# piezo-preamp-tickler_V2-RevA-01.net
KiCad netlist of a schematic drawn in EAGLE
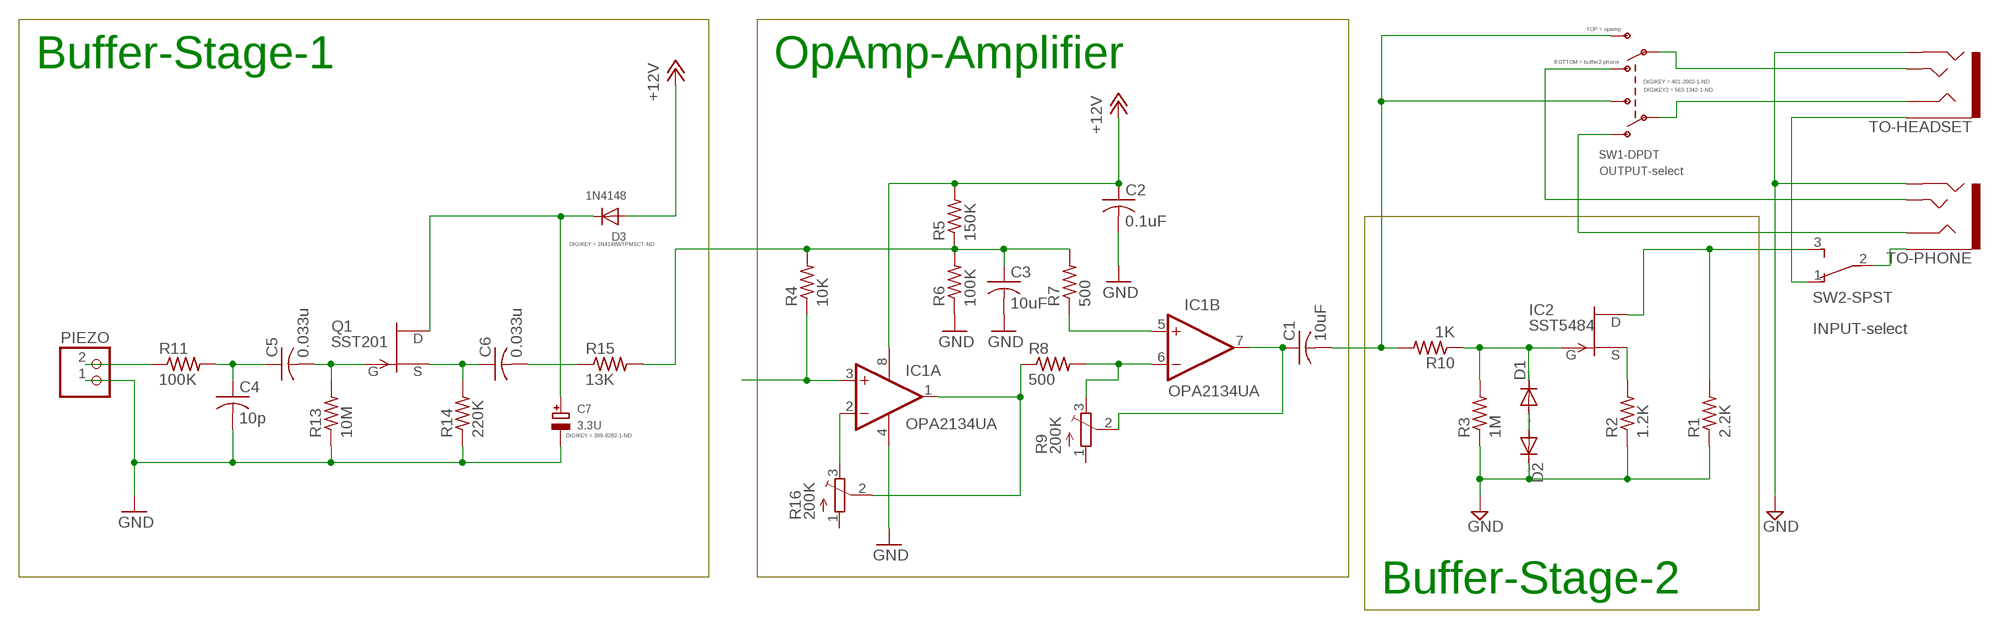
[diagram p0: schematic, sheet 1]
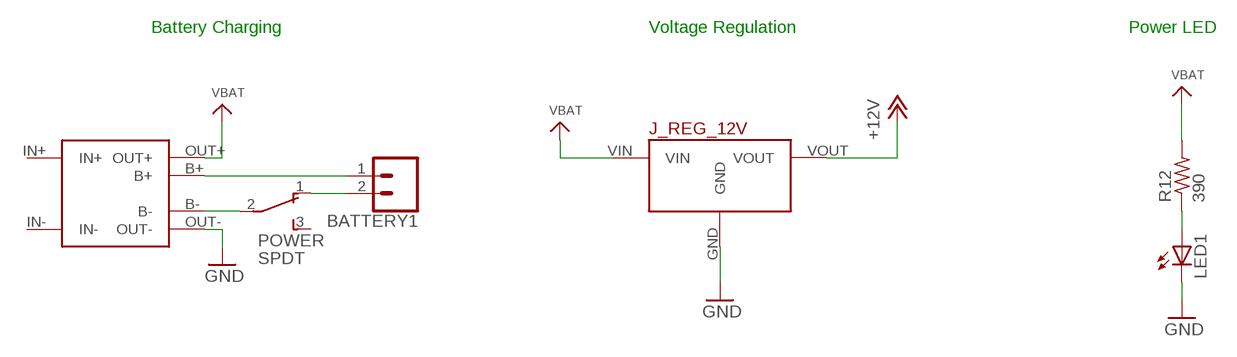
[diagram p1: schematic, sheet 2]

(export (version "E")
  (design (tool "Eeschema 10.0.6"))
  (components
    (comp (ref "C1")
      (value "10uF")
      (footprint "eagle-import:C0805K")
      (libsource (lib "eagle-import") (part "C-USC0805K"))
    )
    (comp (ref "C2")
      (value "0.1uF")
      (footprint "eagle-import:C0805K")
      (libsource (lib "eagle-import") (part "C-USC0805K"))
    )
    (comp (ref "C3")
      (value "10uF")
      (footprint "eagle-import:C0805K")
      (libsource (lib "eagle-import") (part "C-USC0805K"))
    )
    (comp (ref "C4")
      (value "10p")
      (footprint "eagle-import:C0805K")
      (libsource (lib "eagle-import") (part "C-USC0805K"))
    )
    (comp (ref "C5")
      (value "0.033u")
      (footprint "eagle-import:C0805K")
      (libsource (lib "eagle-import") (part "C-USC0805K"))
    )
    (comp (ref "C6")
      (value "0.033u")
      (footprint "eagle-import:C0805K")
      (libsource (lib "eagle-import") (part "C-USC0805K"))
    )
    (comp (ref "C7")
      (value "3.3U")
      (footprint "eagle-import:EIA3216-18_A-R")
      (fields (field (name "DIGIKEY") "399-8282-1-ND"))
      (libsource (lib "eagle-import") (part "CAP_TANTALUMA/3216_REFLOW"))
    )
    (comp (ref "D1")
      (value "DIODE-SOD123")
      (footprint "eagle-import:SOD123")
      (libsource (lib "eagle-import") (part "DIODE-SOD123"))
    )
    (comp (ref "D2")
      (value "DIODE-SOD123")
      (footprint "eagle-import:SOD123")
      (libsource (lib "eagle-import") (part "DIODE-SOD123"))
    )
    (comp (ref "D3")
      (value "1N4148")
      (footprint "eagle-import:SOD-123")
      (fields (field (name "DIGIKEY") "1N4148WTPMSCT-ND"))
      (libsource (lib "eagle-import") (part "DIODESOD-123"))
    )
    (comp (ref "IC1")
      (value "OPA2134UA")
      (footprint "eagle-import:SO08")
      (libsource (lib "eagle-import") (part "OPA2UA134"))
    )
    (comp (ref "IC2")
      (value "SST5484")
      (footprint "eagle-import:SOT23")
      (libsource (lib "eagle-import") (part "?548SST4"))
    )
    (comp (ref "PIEZO")
      (value "JST_2PIN-THM")
      (footprint "eagle-import:JST-PH-2-THM")
      (libsource (lib "eagle-import") (part "JST_2PIN-THM"))
    )
    (comp (ref "Q1")
      (value "SST201")
      (footprint "eagle-import:SOT23")
      (libsource (lib "eagle-import") (part "?20SST1"))
    )
    (comp (ref "R1")
      (value "2.2K")
      (footprint "eagle-import:R0603")
      (libsource (lib "eagle-import") (part "R-US_R0603"))
    )
    (comp (ref "R2")
      (value "1.2K")
      (footprint "eagle-import:R0603")
      (libsource (lib "eagle-import") (part "R-US_R0603"))
    )
    (comp (ref "R3")
      (value "1M")
      (footprint "eagle-import:R0603")
      (libsource (lib "eagle-import") (part "R-US_R0603"))
    )
    (comp (ref "R4")
      (value "10K")
      (footprint "eagle-import:R0603")
      (libsource (lib "eagle-import") (part "R-US_R0603"))
    )
    (comp (ref "R5")
      (value "150K")
      (footprint "eagle-import:R0603")
      (libsource (lib "eagle-import") (part "R-US_R0603"))
    )
    (comp (ref "R6")
      (value "100K")
      (footprint "eagle-import:R0603")
      (libsource (lib "eagle-import") (part "R-US_R0603"))
    )
    (comp (ref "R7")
      (value "500")
      (footprint "eagle-import:R0603")
      (libsource (lib "eagle-import") (part "R-US_R0603"))
    )
    (comp (ref "R8")
      (value "500")
      (footprint "eagle-import:R0603")
      (libsource (lib "eagle-import") (part "R-US_R0603"))
    )
    (comp (ref "R9")
      (value "200K")
      (footprint "eagle-import:TC33X")
      (libsource (lib "eagle-import") (part "TRIMPOTTC33X"))
    )
    (comp (ref "R10")
      (value "1K")
      (footprint "eagle-import:R0603")
      (libsource (lib "eagle-import") (part "R-US_R0603"))
    )
    (comp (ref "R11")
      (value "100K")
      (footprint "eagle-import:R0603")
      (libsource (lib "eagle-import") (part "R-US_R0603"))
    )
    (comp (ref "R13")
      (value "10M")
      (footprint "eagle-import:R0603")
      (libsource (lib "eagle-import") (part "R-US_R0603"))
    )
    (comp (ref "R14")
      (value "220K")
      (footprint "eagle-import:R0603")
      (libsource (lib "eagle-import") (part "R-US_R0603"))
    )
    (comp (ref "R15")
      (value "13K")
      (footprint "eagle-import:R0603")
      (libsource (lib "eagle-import") (part "R-US_R0603"))
    )
    (comp (ref "R16")
      (value "200K")
      (footprint "eagle-import:TC33X")
      (libsource (lib "eagle-import") (part "TRIMPOTTC33X"))
    )
    (comp (ref "SW1-DPDT")
      (value "OUTPUT-select")
      (footprint "eagle-import:DPDT_SMT_JS202011SCQN")
      (fields
        (field (name "BOTTOM") "buffer2-phone")
        (field (name "DIGIKEY") "401-2002-1-ND")
        (field (name "DIGIKEY2") "563-1342-1-ND")
        (field (name "TOP") "opamp")
      )
      (libsource (lib "eagle-import") (part "SWITCH_DPDT"))
    )
    (comp (ref "SW2-SPST")
      (value "INPUT-select")
      (footprint "eagle-import:SWITCH_SPDT-TE-CONNECT")
      (libsource (lib "eagle-import") (part "SWITCH_SPDTTE-CONNECT"))
    )
    (comp (ref "TO-HEADSET")
      (value "AUDIO-JACK3LGPADS")
      (footprint "eagle-import:AUDIO-JACK-TRRS-SMD")
      (libsource (lib "eagle-import") (part "AUDIO-JACK3LGPADS"))
    )
    (comp (ref "TO-PHONE")
      (value "AUDIO-JACK3LGPADS")
      (footprint "eagle-import:AUDIO-JACK-TRRS-SMD")
      (libsource (lib "eagle-import") (part "AUDIO-JACK3LGPADS"))
    )
    (comp (ref "BATTERY1")
      (value "CONN_02LOCK")
      (footprint "eagle-import:1X02_LOCK")
      (libsource (lib "eagle-import") (part "CONN_02LOCK"))
    )
    (comp (ref "J_REG_12V")
      (value "POLOLU_VOLTAGE_REGULATORS_3PIN")
      (footprint "eagle-import:POLOLU_5V-12V_STEPUP_U3V12F5-U3V12F12")
      (libsource (lib "eagle-import") (part "POLOLU_VOLTAGE_REGULATORS_3PIN"))
    )
    (comp (ref "LED1")
      (value "LED3MM")
      (footprint "eagle-import:LED3MM")
      (libsource (lib "eagle-import") (part "LED3MM"))
    )
    (comp (ref "POWER")
      (value "SPDT")
      (footprint "eagle-import:SWITCH_SPDT-TE-CONNECT")
      (libsource (lib "eagle-import") (part "SWITCH_SPDTTE-CONNECT"))
    )
    (comp (ref "R12")
      (value "390")
      (footprint "eagle-import:R0805")
      (libsource (lib "eagle-import") (part "R-US_R0805"))
    )
    (comp (ref "USB-LIPO-CHARGER")
      (value "TP4056-MODULE")
      (footprint "eagle-import:TP4056-LITHIUM-PROTECTED-MODULE")
      (libsource (lib "eagle-import") (part "TP4056-MODULE"))
    )
  )
  (nets
    (net (code "1") (name "+12V") (class "Default")
      (node (ref "C2") (pin "1") (pinfunction "1_1") (pintype "passive"))
      (node (ref "D3") (pin "A") (pinfunction "A_A") (pintype "passive"))
      (node (ref "IC1") (pin "8") (pinfunction "V+_8") (pintype "power_in"))
      (node (ref "J_REG_12V") (pin "VOUT") (pinfunction "VOUT_VOUT") (pintype "bidirectional"))
      (node (ref "R5") (pin "2") (pinfunction "2_2") (pintype "passive"))
    )
    (net (code "2") (name "GND") (class "Default")
      (node (ref "C2") (pin "2") (pinfunction "2_2") (pintype "passive"))
      (node (ref "C3") (pin "2") (pinfunction "2_2") (pintype "passive"))
      (node (ref "C4") (pin "2") (pinfunction "2_2") (pintype "passive"))
      (node (ref "C7") (pin "-") (pinfunction "-_-") (pintype "passive"))
      (node (ref "D2") (pin "C") (pinfunction "C_C") (pintype "passive"))
      (node (ref "IC1") (pin "4") (pinfunction "V-_4") (pintype "power_in"))
      (node (ref "J_REG_12V") (pin "GND") (pinfunction "GND_GND") (pintype "bidirectional"))
      (node (ref "LED1") (pin "K") (pinfunction "C_K") (pintype "passive"))
      (node (ref "PIEZO") (pin "1") (pinfunction "2_1") (pintype "passive"))
      (node (ref "R1") (pin "1") (pinfunction "1_1") (pintype "passive"))
      (node (ref "R13") (pin "1") (pinfunction "1_1") (pintype "passive"))
      (node (ref "R14") (pin "1") (pinfunction "1_1") (pintype "passive"))
      (node (ref "R2") (pin "1") (pinfunction "1_1") (pintype "passive"))
      (node (ref "R3") (pin "1") (pinfunction "1_1") (pintype "passive"))
      (node (ref "R6") (pin "1") (pinfunction "1_1") (pintype "passive"))
      (node (ref "TO-HEADSET") (pin "RING2") (pinfunction "RING2_RING2") (pintype "bidirectional"))
      (node (ref "TO-PHONE") (pin "RING2") (pinfunction "RING2_RING2") (pintype "bidirectional"))
      (node (ref "USB-LIPO-CHARGER") (pin "OUT-") (pinfunction "OUT-_OUT-") (pintype "power_in"))
    )
    (net (code "3") (name "IN+") (class "Default")
      (node (ref "USB-LIPO-CHARGER") (pin "IN+") (pinfunction "IN+_IN+") (pintype "power_in"))
    )
    (net (code "4") (name "IN-") (class "Default")
      (node (ref "USB-LIPO-CHARGER") (pin "IN-") (pinfunction "IN-_IN-") (pintype "power_in"))
    )
    (net (code "5") (name "Net-(BATTERY1-Pad1)") (class "Default")
      (node (ref "BATTERY1") (pin "1") (pinfunction "1_1") (pintype "passive"))
      (node (ref "USB-LIPO-CHARGER") (pin "B+") (pinfunction "B+_B+") (pintype "power_in"))
    )
    (net (code "6") (name "Net-(BATTERY1-Pad2)") (class "Default")
      (node (ref "BATTERY1") (pin "2") (pinfunction "2_2") (pintype "passive"))
      (node (ref "POWER") (pin "1") (pinfunction "1_1") (pintype "passive"))
    )
    (net (code "7") (name "Net-(C3-Pad1)") (class "Default")
      (node (ref "C3") (pin "1") (pinfunction "1_1") (pintype "passive"))
      (node (ref "R15") (pin "2") (pinfunction "2_2") (pintype "passive"))
      (node (ref "R4") (pin "2") (pinfunction "2_2") (pintype "passive"))
      (node (ref "R5") (pin "1") (pinfunction "1_1") (pintype "passive"))
      (node (ref "R6") (pin "2") (pinfunction "2_2") (pintype "passive"))
      (node (ref "R7") (pin "2") (pinfunction "2_2") (pintype "passive"))
    )
    (net (code "8") (name "Net-(C4-Pad1)") (class "Default")
      (node (ref "C4") (pin "1") (pinfunction "1_1") (pintype "passive"))
      (node (ref "C5") (pin "1") (pinfunction "1_1") (pintype "passive"))
      (node (ref "R11") (pin "2") (pinfunction "2_2") (pintype "passive"))
    )
    (net (code "9") (name "Net-(C6-Pad2)") (class "Default")
      (node (ref "C6") (pin "2") (pinfunction "2_2") (pintype "passive"))
      (node (ref "R15") (pin "1") (pinfunction "1_1") (pintype "passive"))
    )
    (net (code "10") (name "Net-(D1-PadA)") (class "Default")
      (node (ref "D1") (pin "A") (pinfunction "A_A") (pintype "passive"))
      (node (ref "D2") (pin "A") (pinfunction "A_A") (pintype "passive"))
    )
    (net (code "11") (name "Net-(IC1A-+IN)") (class "Default")
      (node (ref "IC1") (pin "3") (pinfunction "+IN_3") (pintype "input"))
      (node (ref "R4") (pin "1") (pinfunction "1_1") (pintype "passive"))
    )
    (net (code "12") (name "Net-(IC1A--IN)") (class "Default")
      (node (ref "IC1") (pin "2") (pinfunction "-IN_2") (pintype "input"))
      (node (ref "R16") (pin "3") (pinfunction "E_3") (pintype "passive"))
    )
    (net (code "13") (name "Net-(IC1A-OUT)") (class "Default")
      (node (ref "IC1") (pin "1") (pinfunction "OUT_1") (pintype "output"))
      (node (ref "R16") (pin "2") (pinfunction "S_2") (pintype "passive"))
      (node (ref "R8") (pin "1") (pinfunction "1_1") (pintype "passive"))
    )
    (net (code "14") (name "Net-(IC1B-+IN)") (class "Default")
      (node (ref "IC1") (pin "5") (pinfunction "+IN_5") (pintype "input"))
      (node (ref "R7") (pin "1") (pinfunction "1_1") (pintype "passive"))
    )
    (net (code "15") (name "Net-(IC1B--IN)") (class "Default")
      (node (ref "IC1") (pin "6") (pinfunction "-IN_6") (pintype "input"))
      (node (ref "R8") (pin "2") (pinfunction "2_2") (pintype "passive"))
      (node (ref "R9") (pin "3") (pinfunction "E_3") (pintype "passive"))
    )
    (net (code "16") (name "Net-(IC1B-OUT)") (class "Default")
      (node (ref "C1") (pin "1") (pinfunction "1_1") (pintype "passive"))
      (node (ref "IC1") (pin "7") (pinfunction "OUT_7") (pintype "output"))
      (node (ref "R9") (pin "2") (pinfunction "S_2") (pintype "passive"))
    )
    (net (code "17") (name "Net-(IC2-D)") (class "Default")
      (node (ref "IC2") (pin "1") (pinfunction "D_1") (pintype "passive"))
      (node (ref "R1") (pin "2") (pinfunction "2_2") (pintype "passive"))
      (node (ref "SW2-SPST") (pin "3") (pinfunction "3_3") (pintype "passive"))
    )
    (net (code "18") (name "Net-(IC2-G)") (class "Default")
      (node (ref "D1") (pin "C") (pinfunction "C_C") (pintype "passive"))
      (node (ref "IC2") (pin "3") (pinfunction "G_3") (pintype "passive"))
      (node (ref "R10") (pin "1") (pinfunction "1_1") (pintype "passive"))
      (node (ref "R3") (pin "2") (pinfunction "2_2") (pintype "passive"))
    )
    (net (code "19") (name "Net-(IC2-S)") (class "Default")
      (node (ref "IC2") (pin "2") (pinfunction "S_2") (pintype "passive"))
      (node (ref "R2") (pin "2") (pinfunction "2_2") (pintype "passive"))
    )
    (net (code "20") (name "Net-(LED1-PadA)") (class "Default")
      (node (ref "LED1") (pin "A") (pinfunction "A_A") (pintype "passive"))
      (node (ref "R12") (pin "1") (pinfunction "1_1") (pintype "passive"))
    )
    (net (code "21") (name "Net-(PIEZO-1)") (class "Default")
      (node (ref "PIEZO") (pin "2") (pinfunction "1_2") (pintype "passive"))
      (node (ref "R11") (pin "1") (pinfunction "1_1") (pintype "passive"))
    )
    (net (code "22") (name "Net-(POWER-Pad2)") (class "Default")
      (node (ref "POWER") (pin "2") (pinfunction "2_2") (pintype "passive"))
      (node (ref "USB-LIPO-CHARGER") (pin "B-") (pinfunction "B-_B-") (pintype "power_in"))
    )
    (net (code "23") (name "Net-(Q1-D)") (class "Default")
      (node (ref "C7") (pin "+") (pinfunction "+_+") (pintype "passive"))
      (node (ref "D3") (pin "C") (pinfunction "C_C") (pintype "passive"))
      (node (ref "Q1") (pin "1") (pinfunction "D_1") (pintype "passive"))
    )
    (net (code "24") (name "Net-(Q1-G)") (class "Default")
      (node (ref "C5") (pin "2") (pinfunction "2_2") (pintype "passive"))
      (node (ref "Q1") (pin "3") (pinfunction "G_3") (pintype "passive"))
      (node (ref "R13") (pin "2") (pinfunction "2_2") (pintype "passive"))
    )
    (net (code "25") (name "Net-(Q1-S)") (class "Default")
      (node (ref "C6") (pin "1") (pinfunction "1_1") (pintype "passive"))
      (node (ref "Q1") (pin "2") (pinfunction "S_2") (pintype "passive"))
      (node (ref "R14") (pin "2") (pinfunction "2_2") (pintype "passive"))
    )
    (net (code "26") (name "Net-(SW1-DPDT-O1)") (class "Default")
      (node (ref "SW1-DPDT") (pin "P$1") (pinfunction "O1_P$1") (pintype "passive"))
      (node (ref "TO-PHONE") (pin "RING1") (pinfunction "RING1_RING1") (pintype "bidirectional"))
    )
    (net (code "27") (name "Net-(SW1-DPDT-O2)") (class "Default")
      (node (ref "SW1-DPDT") (pin "P$6") (pinfunction "O2_P$6") (pintype "passive"))
      (node (ref "TO-PHONE") (pin "TIP") (pinfunction "TIP_TIP") (pintype "bidirectional"))
    )
    (net (code "28") (name "Net-(SW1-DPDT-P1)") (class "Default")
      (node (ref "SW1-DPDT") (pin "P$2") (pinfunction "P1_P$2") (pintype "passive"))
      (node (ref "TO-HEADSET") (pin "RING1") (pinfunction "RING1_RING1") (pintype "bidirectional"))
    )
    (net (code "29") (name "Net-(SW1-DPDT-P2)") (class "Default")
      (node (ref "SW1-DPDT") (pin "P$5") (pinfunction "P2_P$5") (pintype "passive"))
      (node (ref "TO-HEADSET") (pin "TIP") (pinfunction "TIP_TIP") (pintype "bidirectional"))
    )
    (net (code "30") (name "Net-(SW1-DPDT-S1)") (class "Default")
      (node (ref "C1") (pin "2") (pinfunction "2_2") (pintype "passive"))
      (node (ref "R10") (pin "2") (pinfunction "2_2") (pintype "passive"))
      (node (ref "SW1-DPDT") (pin "P$3") (pinfunction "S1_P$3") (pintype "passive"))
      (node (ref "SW1-DPDT") (pin "P$4") (pinfunction "S2_P$4") (pintype "passive"))
    )
    (net (code "31") (name "Net-(SW2-SPST-Pad1)") (class "Default")
      (node (ref "SW2-SPST") (pin "1") (pinfunction "1_1") (pintype "passive"))
      (node (ref "TO-HEADSET") (pin "EARTH") (pinfunction "EARTH_EARTH") (pintype "bidirectional"))
    )
    (net (code "32") (name "Net-(SW2-SPST-Pad2)") (class "Default")
      (node (ref "SW2-SPST") (pin "2") (pinfunction "2_2") (pintype "passive"))
      (node (ref "TO-PHONE") (pin "EARTH") (pinfunction "EARTH_EARTH") (pintype "bidirectional"))
    )
    (net (code "33") (name "VBAT") (class "Default")
      (node (ref "J_REG_12V") (pin "VIN") (pinfunction "VIN_VIN") (pintype "bidirectional"))
      (node (ref "R12") (pin "2") (pinfunction "2_2") (pintype "passive"))
      (node (ref "USB-LIPO-CHARGER") (pin "OUT+") (pinfunction "OUT+_OUT+") (pintype "power_in"))
    )
    (net (code "34") (name "unconnected-(POWER-Pad3)") (class "Default")
      (node (ref "POWER") (pin "3") (pinfunction "3_3") (pintype "passive"))
    )
    (net (code "35") (name "unconnected-(R9-A-Pad1)") (class "Default")
      (node (ref "R9") (pin "1") (pinfunction "A_1") (pintype "passive"))
    )
    (net (code "36") (name "unconnected-(R16-A-Pad1)") (class "Default")
      (node (ref "R16") (pin "1") (pinfunction "A_1") (pintype "passive"))
    )
  )
)
